# RTI-Dome-Shutter-ESP32.net
KiCad netlist of a schematic drawn in EAGLE
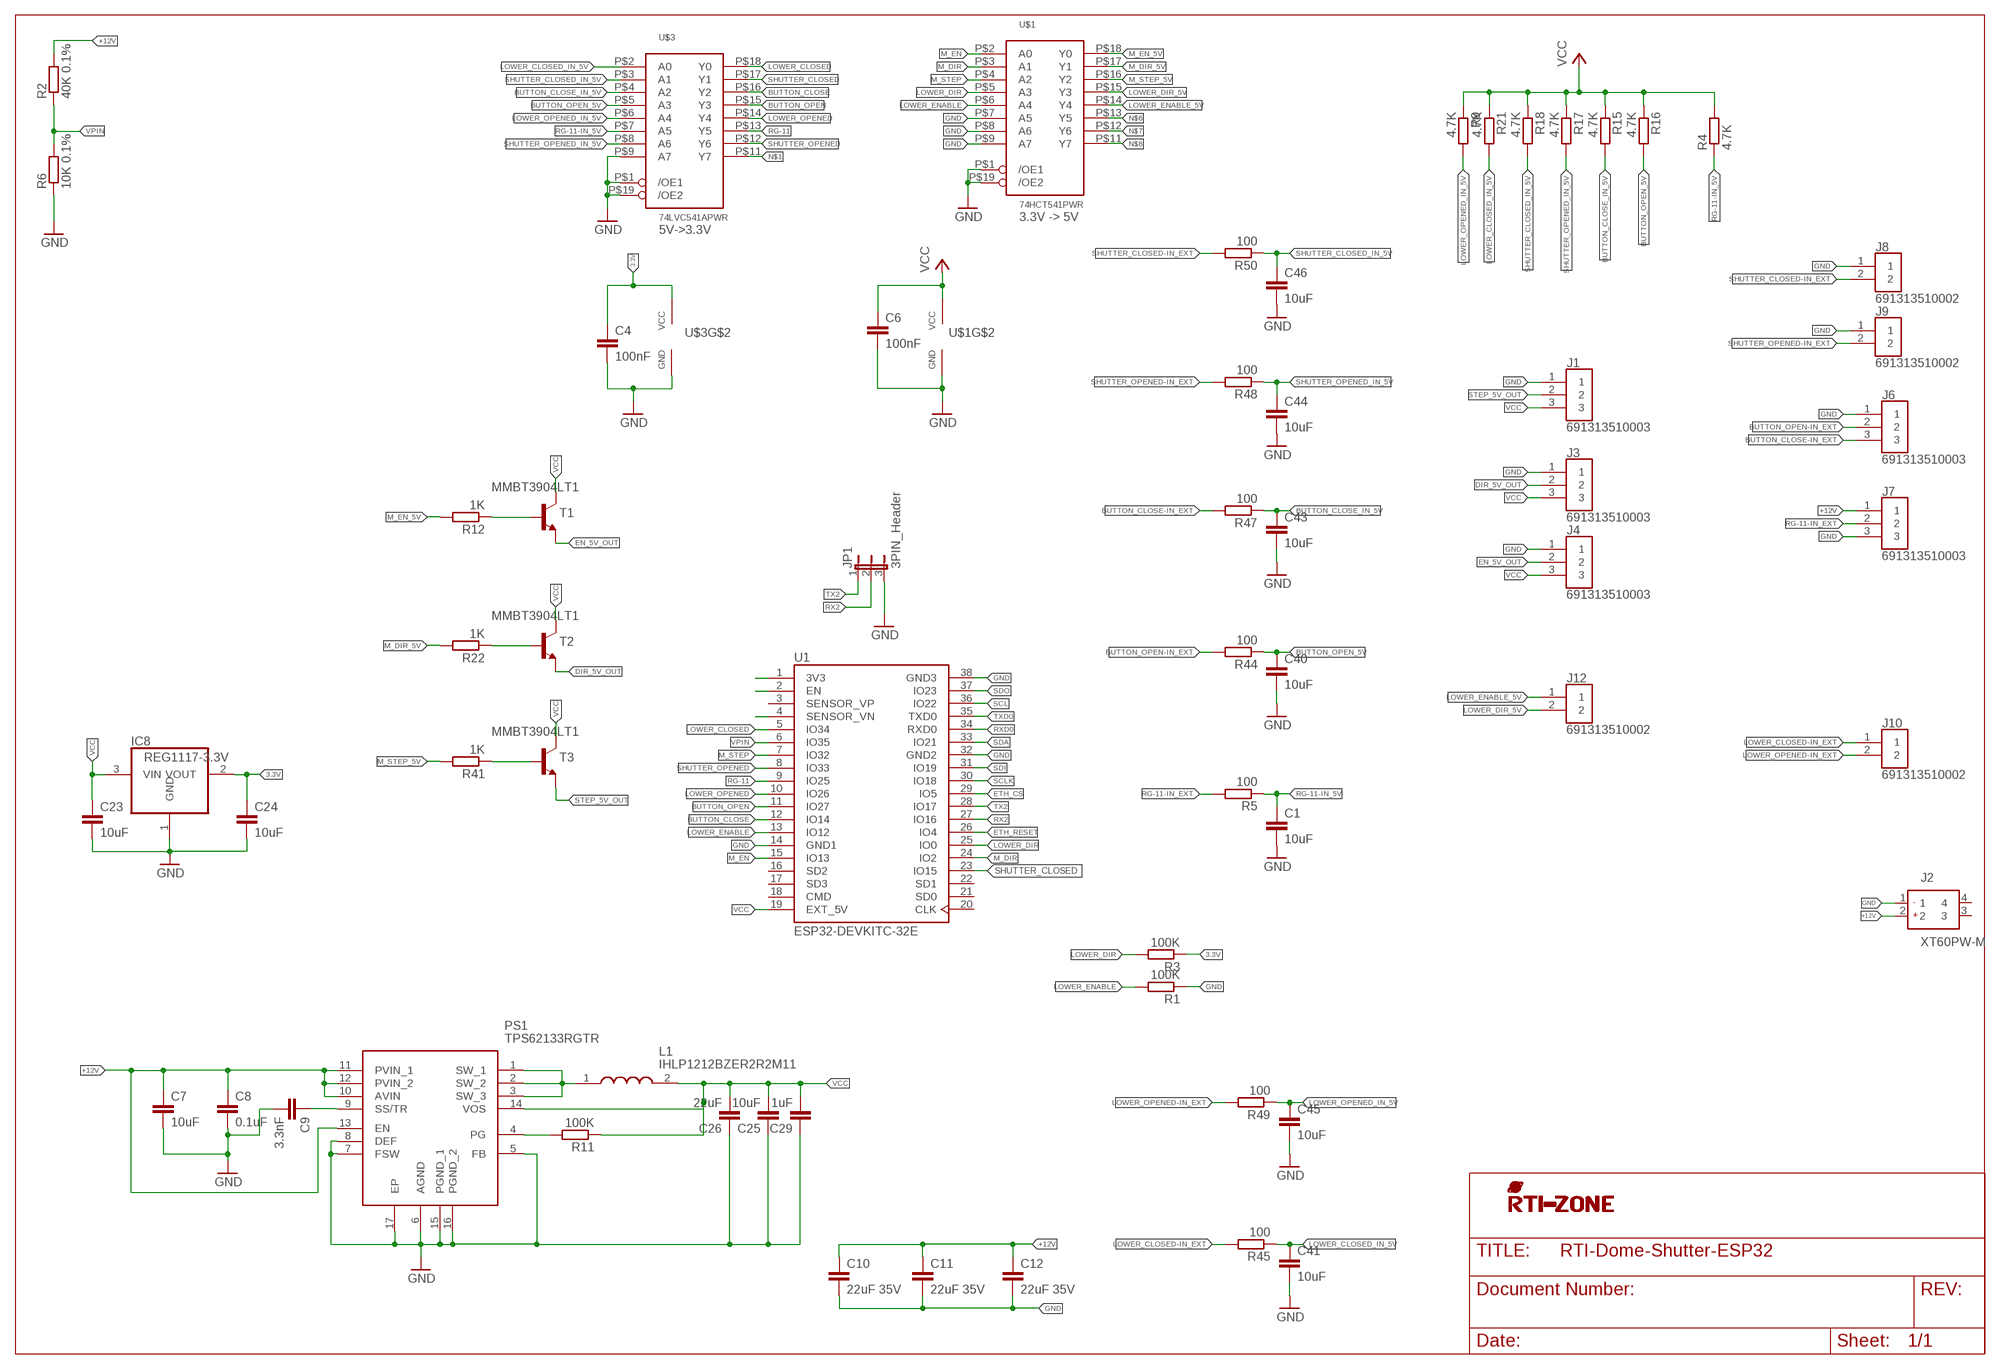
[diagram p0: schematic, sheet 1]

(export (version "E")
  (design (tool "Eeschema 10.0.6"))
  (components
    (comp (ref "C1")
      (value "10uF")
      (footprint "eagle-import:C0603")
      (fields (field (name "MPN") "CC0805KKX5R8BB106"))
      (libsource (lib "eagle-import") (part "C-EU'0603'"))
    )
    (comp (ref "C4")
      (value "100nF")
      (footprint "eagle-import:C0603")
      (fields (field (name "MPN") "0805YD104KAT2A"))
      (libsource (lib "eagle-import") (part "C-EU'0603'"))
    )
    (comp (ref "C6")
      (value "100nF")
      (footprint "eagle-import:C0603")
      (fields (field (name "MPN") "0805YD104KAT2A"))
      (libsource (lib "eagle-import") (part "C-EU'0603'"))
    )
    (comp (ref "C7")
      (value "10uF")
      (footprint "eagle-import:C1206")
      (libsource (lib "eagle-import") (part "C-EUC1206"))
    )
    (comp (ref "C8")
      (value "0.1uF")
      (footprint "eagle-import:C1206")
      (libsource (lib "eagle-import") (part "C-EUC1206"))
    )
    (comp (ref "C9")
      (value "3.3nF")
      (footprint "eagle-import:C0805")
      (libsource (lib "eagle-import") (part "C-EUC0805"))
    )
    (comp (ref "C10")
      (value "22uF 35V")
      (footprint "eagle-import:C1206")
      (libsource (lib "eagle-import") (part "C-EUC1206"))
    )
    (comp (ref "C11")
      (value "22uF 35V")
      (footprint "eagle-import:C1206")
      (libsource (lib "eagle-import") (part "C-EUC1206"))
    )
    (comp (ref "C12")
      (value "22uF 35V")
      (footprint "eagle-import:C1206")
      (libsource (lib "eagle-import") (part "C-EUC1206"))
    )
    (comp (ref "C23")
      (value "10uF")
      (footprint "eagle-import:C0603")
      (fields (field (name "MPN") "CC0805KKX5R8BB106"))
      (libsource (lib "eagle-import") (part "C-EU'0603'"))
    )
    (comp (ref "C24")
      (value "10uF")
      (footprint "eagle-import:C0603")
      (fields (field (name "MPN") "CC0805KKX5R8BB106"))
      (libsource (lib "eagle-import") (part "C-EU'0603'"))
    )
    (comp (ref "C25")
      (value "10uF")
      (footprint "eagle-import:C0805")
      (libsource (lib "eagle-import") (part "C-EUC0805"))
    )
    (comp (ref "C26")
      (value "22uF")
      (footprint "eagle-import:C0805")
      (libsource (lib "eagle-import") (part "C-EUC0805"))
    )
    (comp (ref "C29")
      (value "1uF")
      (footprint "eagle-import:C0805")
      (libsource (lib "eagle-import") (part "C-EUC0805"))
    )
    (comp (ref "C40")
      (value "10uF")
      (footprint "eagle-import:C0603")
      (fields (field (name "MPN") "CC0805KKX5R8BB106"))
      (libsource (lib "eagle-import") (part "C-EU'0603'"))
    )
    (comp (ref "C41")
      (value "10uF")
      (footprint "eagle-import:C0603")
      (fields (field (name "MPN") "CC0805KKX5R8BB106"))
      (libsource (lib "eagle-import") (part "C-EU'0603'"))
    )
    (comp (ref "C43")
      (value "10uF")
      (footprint "eagle-import:C0603")
      (fields (field (name "MPN") "CC0805KKX5R8BB106"))
      (libsource (lib "eagle-import") (part "C-EU'0603'"))
    )
    (comp (ref "C44")
      (value "10uF")
      (footprint "eagle-import:C0603")
      (fields (field (name "MPN") "CC0805KKX5R8BB106"))
      (libsource (lib "eagle-import") (part "C-EU'0603'"))
    )
    (comp (ref "C45")
      (value "10uF")
      (footprint "eagle-import:C0603")
      (fields (field (name "MPN") "CC0805KKX5R8BB106"))
      (libsource (lib "eagle-import") (part "C-EU'0603'"))
    )
    (comp (ref "C46")
      (value "10uF")
      (footprint "eagle-import:C0603")
      (fields (field (name "MPN") "CC0805KKX5R8BB106"))
      (libsource (lib "eagle-import") (part "C-EU'0603'"))
    )
    (comp (ref "IC8")
      (value "REG1117-3.3V")
      (footprint "eagle-import:SOT223")
      (fields (field (name "MPN") "REG1117") (field (name "MPN_1") "REG1117-3.3/2K5"))
      (libsource (lib "eagle-import") (part "REG1117"))
    )
    (comp (ref "J1")
      (value "691313510003")
      (footprint "eagle-import:691313510003")
      (fields (field (name "MOUSER_PART_NUMBER") "710-691313510003"))
      (libsource (lib "eagle-import") (part "691313510003"))
    )
    (comp (ref "J2")
      (value "XT60PW-M")
      (footprint "eagle-import:XT60PWM")
      (fields (field (name "LCSC_PART") "C98732"))
      (libsource (lib "eagle-import") (part "XT60PW-M"))
    )
    (comp (ref "J3")
      (value "691313510003")
      (footprint "eagle-import:691313510003")
      (fields (field (name "MOUSER_PART_NUMBER") "710-691313510003"))
      (libsource (lib "eagle-import") (part "691313510003"))
    )
    (comp (ref "J4")
      (value "691313510003")
      (footprint "eagle-import:691313510003")
      (fields (field (name "MOUSER_PART_NUMBER") "710-691313510003"))
      (libsource (lib "eagle-import") (part "691313510003"))
    )
    (comp (ref "J6")
      (value "691313510003")
      (footprint "eagle-import:691313510003")
      (fields (field (name "MOUSER_PART_NUMBER") "710-691313510003"))
      (libsource (lib "eagle-import") (part "691313510003"))
    )
    (comp (ref "J7")
      (value "691313510003")
      (footprint "eagle-import:691313510003")
      (fields (field (name "MOUSER_PART_NUMBER") "710-691313510003"))
      (libsource (lib "eagle-import") (part "691313510003"))
    )
    (comp (ref "J8")
      (value "691313510002")
      (footprint "eagle-import:SHDRRA2W100P0X508_1X2_1216X120")
      (fields (field (name "MOUSER_PART_NUMBER") "710-691313510002"))
      (libsource (lib "eagle-import") (part "691313510002"))
    )
    (comp (ref "J9")
      (value "691313510002")
      (footprint "eagle-import:SHDRRA2W100P0X508_1X2_1216X120")
      (fields (field (name "MOUSER_PART_NUMBER") "710-691313510002"))
      (libsource (lib "eagle-import") (part "691313510002"))
    )
    (comp (ref "J10")
      (value "691313510002")
      (footprint "eagle-import:SHDRRA2W100P0X508_1X2_1216X120")
      (fields (field (name "MOUSER_PART_NUMBER") "710-691313510002"))
      (libsource (lib "eagle-import") (part "691313510002"))
    )
    (comp (ref "J12")
      (value "691313510002")
      (footprint "eagle-import:SHDRRA2W100P0X508_1X2_1216X120")
      (fields (field (name "MOUSER_PART_NUMBER") "710-691313510002"))
      (libsource (lib "eagle-import") (part "691313510002"))
    )
    (comp (ref "JP1")
      (value "3PIN_Header")
      (footprint "eagle-import:JP2")
      (fields (field (name "LCSC_PART") "C19190477"))
      (libsource (lib "eagle-import") (part "JP2E"))
    )
    (comp (ref "L1")
      (value "IHLP1212BZER2R2M11")
      (footprint "eagle-import:INDPM3630X200N")
      (fields (field (name "LCSC_PART") "C553996") (field (name "MOUSER_PART_NUMBER") "70-IHLP1212BZER2R2M1"))
      (libsource (lib "eagle-import") (part "IHLP1212BZER2R2M11"))
    )
    (comp (ref "PS1")
      (value "TPS62133RGTR")
      (footprint "eagle-import:QFN50P300X300X100-17N")
      (fields (field (name "LCSC_PART") "C73973") (field (name "MOUSER_PART_NUMBER") "595-TPS62133RGTR"))
      (libsource (lib "eagle-import") (part "TPS62133RGTR"))
    )
    (comp (ref "R1")
      (value "100K")
      (footprint "eagle-import:R0603")
      (fields (field (name "MPN") "RT0805FRD07100RL"))
      (libsource (lib "eagle-import") (part "R-EU'0603'"))
    )
    (comp (ref "R2")
      (value "40K 0.1%")
      (footprint "eagle-import:R0603")
      (fields (field (name "MPN") "AT0805BRD07100KL"))
      (libsource (lib "eagle-import") (part "R-EU'0603'"))
    )
    (comp (ref "R3")
      (value "100K")
      (footprint "eagle-import:R0603")
      (fields (field (name "MPN") "RT0805FRD07100RL"))
      (libsource (lib "eagle-import") (part "R-EU'0603'"))
    )
    (comp (ref "R4")
      (value "4.7K")
      (footprint "eagle-import:R0603")
      (fields (field (name "MPN") "RT0805FRE074K7L"))
      (libsource (lib "eagle-import") (part "R-EU'0603'"))
    )
    (comp (ref "R5")
      (value "100")
      (footprint "eagle-import:R0603")
      (fields (field (name "MPN") "RT0805FRD07100RL"))
      (libsource (lib "eagle-import") (part "R-EU'0603'"))
    )
    (comp (ref "R6")
      (value "10K 0.1%")
      (footprint "eagle-import:R0603")
      (fields (field (name "MPN") "AT0805BRD07100KL"))
      (libsource (lib "eagle-import") (part "R-EU'0603'"))
    )
    (comp (ref "R9")
      (value "4.7K")
      (footprint "eagle-import:R0603")
      (fields (field (name "MPN") "RT0805FRE074K7L"))
      (libsource (lib "eagle-import") (part "R-EU'0603'"))
    )
    (comp (ref "R11")
      (value "100K")
      (footprint "eagle-import:R0603")
      (libsource (lib "eagle-import") (part "R-EU_R0603"))
    )
    (comp (ref "R12")
      (value "1K")
      (footprint "eagle-import:R0603")
      (fields (field (name "MPN") "RT0805FRE074K7L"))
      (libsource (lib "eagle-import") (part "R-EU'0603'"))
    )
    (comp (ref "R15")
      (value "4.7K")
      (footprint "eagle-import:R0603")
      (fields (field (name "MPN") "RT0805FRE074K7L"))
      (libsource (lib "eagle-import") (part "R-EU'0603'"))
    )
    (comp (ref "R16")
      (value "4.7K")
      (footprint "eagle-import:R0603")
      (fields (field (name "MPN") "RT0805FRE074K7L"))
      (libsource (lib "eagle-import") (part "R-EU'0603'"))
    )
    (comp (ref "R17")
      (value "4.7K")
      (footprint "eagle-import:R0603")
      (fields (field (name "MPN") "RT0805FRE074K7L"))
      (libsource (lib "eagle-import") (part "R-EU'0603'"))
    )
    (comp (ref "R18")
      (value "4.7K")
      (footprint "eagle-import:R0603")
      (fields (field (name "MPN") "RT0805FRE074K7L"))
      (libsource (lib "eagle-import") (part "R-EU'0603'"))
    )
    (comp (ref "R21")
      (value "4.7K")
      (footprint "eagle-import:R0603")
      (fields (field (name "MPN") "RT0805FRE074K7L"))
      (libsource (lib "eagle-import") (part "R-EU'0603'"))
    )
    (comp (ref "R22")
      (value "1K")
      (footprint "eagle-import:R0603")
      (fields (field (name "MPN") "RT0805FRE074K7L"))
      (libsource (lib "eagle-import") (part "R-EU'0603'"))
    )
    (comp (ref "R41")
      (value "1K")
      (footprint "eagle-import:R0603")
      (fields (field (name "MPN") "RT0805FRE074K7L"))
      (libsource (lib "eagle-import") (part "R-EU'0603'"))
    )
    (comp (ref "R44")
      (value "100")
      (footprint "eagle-import:R0603")
      (fields (field (name "MPN") "RT0805FRD07100RL"))
      (libsource (lib "eagle-import") (part "R-EU'0603'"))
    )
    (comp (ref "R45")
      (value "100")
      (footprint "eagle-import:R0603")
      (fields (field (name "MPN") "RT0805FRD07100RL"))
      (libsource (lib "eagle-import") (part "R-EU'0603'"))
    )
    (comp (ref "R47")
      (value "100")
      (footprint "eagle-import:R0603")
      (fields (field (name "MPN") "RT0805FRD07100RL"))
      (libsource (lib "eagle-import") (part "R-EU'0603'"))
    )
    (comp (ref "R48")
      (value "100")
      (footprint "eagle-import:R0603")
      (fields (field (name "MPN") "RT0805FRD07100RL"))
      (libsource (lib "eagle-import") (part "R-EU'0603'"))
    )
    (comp (ref "R49")
      (value "100")
      (footprint "eagle-import:R0603")
      (fields (field (name "MPN") "RT0805FRD07100RL"))
      (libsource (lib "eagle-import") (part "R-EU'0603'"))
    )
    (comp (ref "R50")
      (value "100")
      (footprint "eagle-import:R0603")
      (fields (field (name "MPN") "RT0805FRD07100RL"))
      (libsource (lib "eagle-import") (part "R-EU'0603'"))
    )
    (comp (ref "T1")
      (value "MMBT3904LT1")
      (footprint "eagle-import:SOT23-BEC")
      (libsource (lib "eagle-import") (part "-NPN-SOT23-BECMMBT3904LT1"))
    )
    (comp (ref "T2")
      (value "MMBT3904LT1")
      (footprint "eagle-import:SOT23-BEC")
      (libsource (lib "eagle-import") (part "-NPN-SOT23-BECMMBT3904LT1"))
    )
    (comp (ref "T3")
      (value "MMBT3904LT1")
      (footprint "eagle-import:SOT23-BEC")
      (libsource (lib "eagle-import") (part "-NPN-SOT23-BECMMBT3904LT1"))
    )
    (comp (ref "U$1")
      (value "74HCT541PWR")
      (footprint "eagle-import:TSSOP20")
      (libsource (lib "eagle-import") (part "74541B"))
    )
    (comp (ref "U$3")
      (value "74LVC541APWR")
      (footprint "eagle-import:TSSOP20")
      (libsource (lib "eagle-import") (part "74541B"))
    )
    (comp (ref "U$4")
      (value "RTI-LOGO_BIG")
      (footprint "eagle-import:LOGO_BIG")
      (libsource (lib "eagle-import") (part "RTI-LOGO_BIG"))
    )
    (comp (ref "U1")
      (value "ESP32-DEVKITC-32E")
      (footprint "eagle-import:MODULE_ESP32-DEVKITC-32D")
      (fields (field (name "MF") "Espressif Systems") (field (name "MP") "ESP32-DEVKITC-32D"))
      (libsource (lib "eagle-import") (part "ESP32-DEVKITC-32D"))
    )
  )
  (nets
    (net (code "1") (name "+12V") (class "Default")
      (node (ref "C10") (pin "1") (pinfunction "1_1") (pintype "passive"))
      (node (ref "C11") (pin "1") (pinfunction "1_1") (pintype "passive"))
      (node (ref "C12") (pin "1") (pinfunction "1_1") (pintype "passive"))
      (node (ref "C7") (pin "1") (pinfunction "1_1") (pintype "passive"))
      (node (ref "C8") (pin "1") (pinfunction "1_1") (pintype "passive"))
      (node (ref "J2") (pin "2") (pinfunction "2_2") (pintype "bidirectional"))
      (node (ref "J7") (pin "1") (pinfunction "1_1") (pintype "bidirectional"))
      (node (ref "PS1") (pin "10") (pinfunction "AVIN_10") (pintype "bidirectional"))
      (node (ref "PS1") (pin "11") (pinfunction "PVIN_1_11") (pintype "bidirectional"))
      (node (ref "PS1") (pin "12") (pinfunction "PVIN_2_12") (pintype "bidirectional"))
      (node (ref "PS1") (pin "13") (pinfunction "EN_13") (pintype "bidirectional"))
      (node (ref "R2") (pin "2") (pinfunction "2_2") (pintype "passive"))
    )
    (net (code "2") (name "3.3V") (class "Default")
      (node (ref "C24") (pin "1") (pinfunction "1_1") (pintype "passive"))
      (node (ref "C4") (pin "1") (pinfunction "1_1") (pintype "passive"))
      (node (ref "IC8") (pin "2") (pinfunction "VOUT_2") (pintype "output"))
      (node (ref "R3") (pin "1") (pinfunction "1_1") (pintype "passive"))
      (node (ref "U$3") (pin "P$20") (pinfunction "VCC_P$20") (pintype "power_in"))
    )
    (net (code "3") (name "BUTTON_CLOSE") (class "Default")
      (node (ref "U$3") (pin "P$16") (pinfunction "Y2_P$16") (pintype "output"))
      (node (ref "U1") (pin "12") (pinfunction "IO14_12") (pintype "bidirectional"))
    )
    (net (code "4") (name "BUTTON_CLOSE-IN_EXT") (class "Default")
      (node (ref "J6") (pin "3") (pinfunction "3_3") (pintype "bidirectional"))
      (node (ref "R47") (pin "2") (pinfunction "2_2") (pintype "passive"))
    )
    (net (code "5") (name "BUTTON_CLOSE_IN_5V") (class "Default")
      (node (ref "C43") (pin "1") (pinfunction "1_1") (pintype "passive"))
      (node (ref "R15") (pin "2") (pinfunction "2_2") (pintype "passive"))
      (node (ref "R47") (pin "1") (pinfunction "1_1") (pintype "passive"))
      (node (ref "U$3") (pin "P$4") (pinfunction "A2_P$4") (pintype "input"))
    )
    (net (code "6") (name "BUTTON_OPEN") (class "Default")
      (node (ref "U$3") (pin "P$15") (pinfunction "Y3_P$15") (pintype "output"))
      (node (ref "U1") (pin "11") (pinfunction "IO27_11") (pintype "bidirectional"))
    )
    (net (code "7") (name "BUTTON_OPEN-IN_EXT") (class "Default")
      (node (ref "J6") (pin "2") (pinfunction "2_2") (pintype "bidirectional"))
      (node (ref "R44") (pin "2") (pinfunction "2_2") (pintype "passive"))
    )
    (net (code "8") (name "BUTTON_OPEN_5V") (class "Default")
      (node (ref "C40") (pin "1") (pinfunction "1_1") (pintype "passive"))
      (node (ref "R16") (pin "2") (pinfunction "2_2") (pintype "passive"))
      (node (ref "R44") (pin "1") (pinfunction "1_1") (pintype "passive"))
      (node (ref "U$3") (pin "P$5") (pinfunction "A3_P$5") (pintype "input"))
    )
    (net (code "9") (name "DIR_5V_OUT") (class "Default")
      (node (ref "J3") (pin "2") (pinfunction "2_2") (pintype "bidirectional"))
      (node (ref "T2") (pin "E") (pinfunction "E_E") (pintype "passive"))
    )
    (net (code "10") (name "EN_5V_OUT") (class "Default")
      (node (ref "J4") (pin "2") (pinfunction "2_2") (pintype "bidirectional"))
      (node (ref "T1") (pin "E") (pinfunction "E_E") (pintype "passive"))
    )
    (net (code "11") (name "ETH_CS") (class "Default")
      (node (ref "U1") (pin "29") (pinfunction "IO5_29") (pintype "bidirectional"))
    )
    (net (code "12") (name "ETH_RESET") (class "Default")
      (node (ref "U1") (pin "26") (pinfunction "IO4_26") (pintype "bidirectional"))
    )
    (net (code "13") (name "GND") (class "Default")
      (node (ref "C1") (pin "2") (pinfunction "2_2") (pintype "passive"))
      (node (ref "C10") (pin "2") (pinfunction "2_2") (pintype "passive"))
      (node (ref "C11") (pin "2") (pinfunction "2_2") (pintype "passive"))
      (node (ref "C12") (pin "2") (pinfunction "2_2") (pintype "passive"))
      (node (ref "C23") (pin "2") (pinfunction "2_2") (pintype "passive"))
      (node (ref "C24") (pin "2") (pinfunction "2_2") (pintype "passive"))
      (node (ref "C25") (pin "1") (pinfunction "1_1") (pintype "passive"))
      (node (ref "C26") (pin "1") (pinfunction "1_1") (pintype "passive"))
      (node (ref "C29") (pin "1") (pinfunction "1_1") (pintype "passive"))
      (node (ref "C4") (pin "2") (pinfunction "2_2") (pintype "passive"))
      (node (ref "C40") (pin "2") (pinfunction "2_2") (pintype "passive"))
      (node (ref "C41") (pin "2") (pinfunction "2_2") (pintype "passive"))
      (node (ref "C43") (pin "2") (pinfunction "2_2") (pintype "passive"))
      (node (ref "C44") (pin "2") (pinfunction "2_2") (pintype "passive"))
      (node (ref "C45") (pin "2") (pinfunction "2_2") (pintype "passive"))
      (node (ref "C46") (pin "2") (pinfunction "2_2") (pintype "passive"))
      (node (ref "C6") (pin "2") (pinfunction "2_2") (pintype "passive"))
      (node (ref "C7") (pin "2") (pinfunction "2_2") (pintype "passive"))
      (node (ref "C8") (pin "2") (pinfunction "2_2") (pintype "passive"))
      (node (ref "C9") (pin "2") (pinfunction "2_2") (pintype "passive"))
      (node (ref "IC8") (pin "1") (pinfunction "GND_1") (pintype "power_in"))
      (node (ref "J1") (pin "1") (pinfunction "1_1") (pintype "bidirectional"))
      (node (ref "J2") (pin "1") (pinfunction "1_1") (pintype "bidirectional"))
      (node (ref "J3") (pin "1") (pinfunction "1_1") (pintype "bidirectional"))
      (node (ref "J4") (pin "1") (pinfunction "1_1") (pintype "bidirectional"))
      (node (ref "J6") (pin "1") (pinfunction "1_1") (pintype "bidirectional"))
      (node (ref "J7") (pin "3") (pinfunction "3_3") (pintype "bidirectional"))
      (node (ref "J8") (pin "1") (pinfunction "1_1") (pintype "bidirectional"))
      (node (ref "J9") (pin "1") (pinfunction "1_1") (pintype "bidirectional"))
      (node (ref "JP1") (pin "3") (pinfunction "3_3") (pintype "passive"))
      (node (ref "PS1") (pin "15") (pinfunction "PGND_1_15") (pintype "bidirectional"))
      (node (ref "PS1") (pin "16") (pinfunction "PGND_2_16") (pintype "bidirectional"))
      (node (ref "PS1") (pin "17") (pinfunction "EP_17") (pintype "bidirectional"))
      (node (ref "PS1") (pin "5") (pinfunction "FB_5") (pintype "bidirectional"))
      (node (ref "PS1") (pin "6") (pinfunction "AGND_6") (pintype "bidirectional"))
      (node (ref "PS1") (pin "7") (pinfunction "FSW_7") (pintype "bidirectional"))
      (node (ref "PS1") (pin "8") (pinfunction "DEF_8") (pintype "bidirectional"))
      (node (ref "R1") (pin "1") (pinfunction "1_1") (pintype "passive"))
      (node (ref "R6") (pin "1") (pinfunction "1_1") (pintype "passive"))
      (node (ref "U$1") (pin "P$1") (pinfunction "/OE1_P$1") (pintype "input"))
      (node (ref "U$1") (pin "P$10") (pinfunction "GND_P$10") (pintype "power_in"))
      (node (ref "U$1") (pin "P$19") (pinfunction "/OE2_P$19") (pintype "input"))
      (node (ref "U$1") (pin "P$7") (pinfunction "A5_P$7") (pintype "input"))
      (node (ref "U$1") (pin "P$8") (pinfunction "A6_P$8") (pintype "input"))
      (node (ref "U$1") (pin "P$9") (pinfunction "A7_P$9") (pintype "input"))
      (node (ref "U$3") (pin "P$1") (pinfunction "/OE1_P$1") (pintype "input"))
      (node (ref "U$3") (pin "P$10") (pinfunction "GND_P$10") (pintype "power_in"))
      (node (ref "U$3") (pin "P$19") (pinfunction "/OE2_P$19") (pintype "input"))
      (node (ref "U$3") (pin "P$9") (pinfunction "A7_P$9") (pintype "input"))
      (node (ref "U1") (pin "14") (pinfunction "GND1_14") (pintype "power_in"))
      (node (ref "U1") (pin "32") (pinfunction "GND2_32") (pintype "power_in"))
      (node (ref "U1") (pin "38") (pinfunction "GND3_38") (pintype "power_in"))
    )
    (net (code "14") (name "LOWER_CLOSED") (class "Default")
      (node (ref "U$3") (pin "P$18") (pinfunction "Y0_P$18") (pintype "output"))
      (node (ref "U1") (pin "5") (pinfunction "IO34_5") (pintype "bidirectional"))
    )
    (net (code "15") (name "LOWER_CLOSED-IN_EXT") (class "Default")
      (node (ref "J10") (pin "1") (pinfunction "1_1") (pintype "bidirectional"))
      (node (ref "R45") (pin "2") (pinfunction "2_2") (pintype "passive"))
    )
    (net (code "16") (name "LOWER_CLOSED_IN_5V") (class "Default")
      (node (ref "C41") (pin "1") (pinfunction "1_1") (pintype "passive"))
      (node (ref "R21") (pin "2") (pinfunction "2_2") (pintype "passive"))
      (node (ref "R45") (pin "1") (pinfunction "1_1") (pintype "passive"))
      (node (ref "U$3") (pin "P$2") (pinfunction "A0_P$2") (pintype "input"))
    )
    (net (code "17") (name "LOWER_DIR") (class "Default")
      (node (ref "R3") (pin "2") (pinfunction "2_2") (pintype "passive"))
      (node (ref "U$1") (pin "P$5") (pinfunction "A3_P$5") (pintype "input"))
      (node (ref "U1") (pin "25") (pinfunction "IO0_25") (pintype "bidirectional"))
    )
    (net (code "18") (name "LOWER_DIR_5V") (class "Default")
      (node (ref "J12") (pin "2") (pinfunction "2_2") (pintype "bidirectional"))
      (node (ref "U$1") (pin "P$15") (pinfunction "Y3_P$15") (pintype "output"))
    )
    (net (code "19") (name "LOWER_ENABLE") (class "Default")
      (node (ref "R1") (pin "2") (pinfunction "2_2") (pintype "passive"))
      (node (ref "U$1") (pin "P$6") (pinfunction "A4_P$6") (pintype "input"))
      (node (ref "U1") (pin "13") (pinfunction "IO12_13") (pintype "bidirectional"))
    )
    (net (code "20") (name "LOWER_ENABLE_5V") (class "Default")
      (node (ref "J12") (pin "1") (pinfunction "1_1") (pintype "bidirectional"))
      (node (ref "U$1") (pin "P$14") (pinfunction "Y4_P$14") (pintype "output"))
    )
    (net (code "21") (name "LOWER_OPENED") (class "Default")
      (node (ref "U$3") (pin "P$14") (pinfunction "Y4_P$14") (pintype "output"))
      (node (ref "U1") (pin "10") (pinfunction "IO26_10") (pintype "bidirectional"))
    )
    (net (code "22") (name "LOWER_OPENED-IN_EXT") (class "Default")
      (node (ref "J10") (pin "2") (pinfunction "2_2") (pintype "bidirectional"))
      (node (ref "R49") (pin "2") (pinfunction "2_2") (pintype "passive"))
    )
    (net (code "23") (name "LOWER_OPENED_IN_5V") (class "Default")
      (node (ref "C45") (pin "1") (pinfunction "1_1") (pintype "passive"))
      (node (ref "R49") (pin "1") (pinfunction "1_1") (pintype "passive"))
      (node (ref "R9") (pin "2") (pinfunction "2_2") (pintype "passive"))
      (node (ref "U$3") (pin "P$6") (pinfunction "A4_P$6") (pintype "input"))
    )
    (net (code "24") (name "M_DIR") (class "Default")
      (node (ref "U$1") (pin "P$3") (pinfunction "A1_P$3") (pintype "input"))
      (node (ref "U1") (pin "24") (pinfunction "IO2_24") (pintype "bidirectional"))
    )
    (net (code "25") (name "M_DIR_5V") (class "Default")
      (node (ref "R22") (pin "2") (pinfunction "2_2") (pintype "passive"))
      (node (ref "U$1") (pin "P$17") (pinfunction "Y1_P$17") (pintype "output"))
    )
    (net (code "26") (name "M_EN") (class "Default")
      (node (ref "U$1") (pin "P$2") (pinfunction "A0_P$2") (pintype "input"))
      (node (ref "U1") (pin "15") (pinfunction "IO13_15") (pintype "bidirectional"))
    )
    (net (code "27") (name "M_EN_5V") (class "Default")
      (node (ref "R12") (pin "2") (pinfunction "2_2") (pintype "passive"))
      (node (ref "U$1") (pin "P$18") (pinfunction "Y0_P$18") (pintype "output"))
    )
    (net (code "28") (name "M_STEP") (class "Default")
      (node (ref "U$1") (pin "P$4") (pinfunction "A2_P$4") (pintype "input"))
      (node (ref "U1") (pin "7") (pinfunction "IO32_7") (pintype "bidirectional"))
    )
    (net (code "29") (name "M_STEP_5V") (class "Default")
      (node (ref "R41") (pin "2") (pinfunction "2_2") (pintype "passive"))
      (node (ref "U$1") (pin "P$16") (pinfunction "Y2_P$16") (pintype "output"))
    )
    (net (code "30") (name "N$1") (class "Default")
      (node (ref "U$3") (pin "P$11") (pinfunction "Y7_P$11") (pintype "output"))
    )
    (net (code "31") (name "N$6") (class "Default")
      (node (ref "U$1") (pin "P$13") (pinfunction "Y5_P$13") (pintype "output"))
    )
    (net (code "32") (name "N$7") (class "Default")
      (node (ref "U$1") (pin "P$12") (pinfunction "Y6_P$12") (pintype "output"))
    )
    (net (code "33") (name "N$8") (class "Default")
      (node (ref "U$1") (pin "P$11") (pinfunction "Y7_P$11") (pintype "output"))
    )
    (net (code "34") (name "Net-(PS1-PG)") (class "Default")
      (node (ref "PS1") (pin "4") (pinfunction "PG_4") (pintype "bidirectional"))
      (node (ref "R11") (pin "2") (pinfunction "2_2") (pintype "passive"))
    )
    (net (code "35") (name "Net-(PS1-SS{slash}TR)") (class "Default")
      (node (ref "C9") (pin "1") (pinfunction "1_1") (pintype "passive"))
      (node (ref "PS1") (pin "9") (pinfunction "SS/TR_9") (pintype "bidirectional"))
    )
    (net (code "36") (name "Net-(PS1-SW_1)") (class "Default")
      (node (ref "L1") (pin "1") (pinfunction "1_1") (pintype "bidirectional"))
      (node (ref "PS1") (pin "1") (pinfunction "SW_1_1") (pintype "bidirectional"))
      (node (ref "PS1") (pin "2") (pinfunction "SW_2_2") (pintype "bidirectional"))
      (node (ref "PS1") (pin "3") (pinfunction "SW_3_3") (pintype "bidirectional"))
    )
    (net (code "37") (name "Net-(R12-Pad1)") (class "Default")
      (node (ref "R12") (pin "1") (pinfunction "1_1") (pintype "passive"))
      (node (ref "T1") (pin "B") (pinfunction "B_B") (pintype "passive"))
    )
    (net (code "38") (name "Net-(R22-Pad1)") (class "Default")
      (node (ref "R22") (pin "1") (pinfunction "1_1") (pintype "passive"))
      (node (ref "T2") (pin "B") (pinfunction "B_B") (pintype "passive"))
    )
    (net (code "39") (name "Net-(R41-Pad1)") (class "Default")
      (node (ref "R41") (pin "1") (pinfunction "1_1") (pintype "passive"))
      (node (ref "T3") (pin "B") (pinfunction "B_B") (pintype "passive"))
    )
    (net (code "40") (name "RG-11") (class "Default")
      (node (ref "U$3") (pin "P$13") (pinfunction "Y5_P$13") (pintype "output"))
      (node (ref "U1") (pin "9") (pinfunction "IO25_9") (pintype "bidirectional"))
    )
    (net (code "41") (name "RG-11-IN_5V") (class "Default")
      (node (ref "C1") (pin "1") (pinfunction "1_1") (pintype "passive"))
      (node (ref "R4") (pin "1") (pinfunction "1_1") (pintype "passive"))
      (node (ref "R5") (pin "1") (pinfunction "1_1") (pintype "passive"))
      (node (ref "U$3") (pin "P$7") (pinfunction "A5_P$7") (pintype "input"))
    )
    (net (code "42") (name "RG-11-IN_EXT") (class "Default")
      (node (ref "J7") (pin "2") (pinfunction "2_2") (pintype "bidirectional"))
      (node (ref "R5") (pin "2") (pinfunction "2_2") (pintype "passive"))
    )
    (net (code "43") (name "RX2") (class "Default")
      (node (ref "JP1") (pin "2") (pinfunction "2_2") (pintype "passive"))
      (node (ref "U1") (pin "27") (pinfunction "IO16_27") (pintype "bidirectional"))
    )
    (net (code "44") (name "RXD0") (class "Default")
      (node (ref "U1") (pin "34") (pinfunction "RXD0_34") (pintype "input"))
    )
    (net (code "45") (name "SCL") (class "Default")
      (node (ref "U1") (pin "36") (pinfunction "IO22_36") (pintype "bidirectional"))
    )
    (net (code "46") (name "SCLK") (class "Default")
      (node (ref "U1") (pin "30") (pinfunction "IO18_30") (pintype "bidirectional"))
    )
    (net (code "47") (name "SDA") (class "Default")
      (node (ref "U1") (pin "33") (pinfunction "IO21_33") (pintype "bidirectional"))
    )
    (net (code "48") (name "SDI") (class "Default")
      (node (ref "U1") (pin "31") (pinfunction "IO19_31") (pintype "bidirectional"))
    )
    (net (code "49") (name "SDO") (class "Default")
      (node (ref "U1") (pin "37") (pinfunction "IO23_37") (pintype "bidirectional"))
    )
    (net (code "50") (name "SHUTTER_CLOSED") (class "Default")
      (node (ref "U$3") (pin "P$17") (pinfunction "Y1_P$17") (pintype "output"))
      (node (ref "U1") (pin "23") (pinfunction "IO15_23") (pintype "bidirectional"))
    )
    (net (code "51") (name "SHUTTER_CLOSED-IN_EXT") (class "Default")
      (node (ref "J8") (pin "2") (pinfunction "2_2") (pintype "bidirectional"))
      (node (ref "R50") (pin "2") (pinfunction "2_2") (pintype "passive"))
    )
    (net (code "52") (name "SHUTTER_CLOSED_IN_5V") (class "Default")
      (node (ref "C46") (pin "1") (pinfunction "1_1") (pintype "passive"))
      (node (ref "R18") (pin "2") (pinfunction "2_2") (pintype "passive"))
      (node (ref "R50") (pin "1") (pinfunction "1_1") (pintype "passive"))
      (node (ref "U$3") (pin "P$3") (pinfunction "A1_P$3") (pintype "input"))
    )
    (net (code "53") (name "SHUTTER_OPENED") (class "Default")
      (node (ref "U$3") (pin "P$12") (pinfunction "Y6_P$12") (pintype "output"))
      (node (ref "U1") (pin "8") (pinfunction "IO33_8") (pintype "bidirectional"))
    )
    (net (code "54") (name "SHUTTER_OPENED-IN_EXT") (class "Default")
      (node (ref "J9") (pin "2") (pinfunction "2_2") (pintype "bidirectional"))
      (node (ref "R48") (pin "2") (pinfunction "2_2") (pintype "passive"))
    )
    (net (code "55") (name "SHUTTER_OPENED_IN_5V") (class "Default")
      (node (ref "C44") (pin "1") (pinfunction "1_1") (pintype "passive"))
      (node (ref "R17") (pin "2") (pinfunction "2_2") (pintype "passive"))
      (node (ref "R48") (pin "1") (pinfunction "1_1") (pintype "passive"))
      (node (ref "U$3") (pin "P$8") (pinfunction "A6_P$8") (pintype "input"))
    )
    (net (code "56") (name "STEP_5V_OUT") (class "Default")
      (node (ref "J1") (pin "2") (pinfunction "2_2") (pintype "bidirectional"))
      (node (ref "T3") (pin "E") (pinfunction "E_E") (pintype "passive"))
    )
    (net (code "57") (name "TX2") (class "Default")
      (node (ref "JP1") (pin "1") (pinfunction "1_1") (pintype "passive"))
      (node (ref "U1") (pin "28") (pinfunction "IO17_28") (pintype "bidirectional"))
    )
    (net (code "58") (name "TXD0") (class "Default")
      (node (ref "U1") (pin "35") (pinfunction "TXD0_35") (pintype "output"))
    )
    (net (code "59") (name "VCC") (class "Default")
      (node (ref "C23") (pin "1") (pinfunction "1_1") (pintype "passive"))
      (node (ref "C25") (pin "2") (pinfunction "2_2") (pintype "passive"))
      (node (ref "C26") (pin "2") (pinfunction "2_2") (pintype "passive"))
      (node (ref "C29") (pin "2") (pinfunction "2_2") (pintype "passive"))
      (node (ref "C6") (pin "1") (pinfunction "1_1") (pintype "passive"))
      (node (ref "IC8") (pin "3") (pinfunction "VIN_3") (pintype "input"))
      (node (ref "J1") (pin "3") (pinfunction "3_3") (pintype "bidirectional"))
      (node (ref "J3") (pin "3") (pinfunction "3_3") (pintype "bidirectional"))
      (node (ref "J4") (pin "3") (pinfunction "3_3") (pintype "bidirectional"))
      (node (ref "L1") (pin "2") (pinfunction "2_2") (pintype "bidirectional"))
      (node (ref "PS1") (pin "14") (pinfunction "VOS_14") (pintype "bidirectional"))
      (node (ref "R11") (pin "1") (pinfunction "1_1") (pintype "passive"))
      (node (ref "R15") (pin "1") (pinfunction "1_1") (pintype "passive"))
      (node (ref "R16") (pin "1") (pinfunction "1_1") (pintype "passive"))
      (node (ref "R17") (pin "1") (pinfunction "1_1") (pintype "passive"))
      (node (ref "R18") (pin "1") (pinfunction "1_1") (pintype "passive"))
      (node (ref "R21") (pin "1") (pinfunction "1_1") (pintype "passive"))
      (node (ref "R4") (pin "2") (pinfunction "2_2") (pintype "passive"))
      (node (ref "R9") (pin "1") (pinfunction "1_1") (pintype "passive"))
      (node (ref "T1") (pin "C") (pinfunction "C_C") (pintype "passive"))
      (node (ref "T2") (pin "C") (pinfunction "C_C") (pintype "passive"))
      (node (ref "T3") (pin "C") (pinfunction "C_C") (pintype "passive"))
      (node (ref "U$1") (pin "P$20") (pinfunction "VCC_P$20") (pintype "power_in"))
      (node (ref "U1") (pin "19") (pinfunction "EXT_5V_19") (pintype "power_in"))
    )
    (net (code "60") (name "VPIN") (class "Default")
      (node (ref "R2") (pin "1") (pinfunction "1_1") (pintype "passive"))
      (node (ref "R6") (pin "2") (pinfunction "2_2") (pintype "passive"))
      (node (ref "U1") (pin "6") (pinfunction "IO35_6") (pintype "bidirectional"))
    )
    (net (code "61") (name "unconnected-(J2-Pad3)") (class "Default")
      (node (ref "J2") (pin "3") (pinfunction "3_3") (pintype "bidirectional"))
    )
    (net (code "62") (name "unconnected-(J2-Pad4)") (class "Default")
      (node (ref "J2") (pin "4") (pinfunction "4_4") (pintype "bidirectional"))
    )
    (net (code "63") (name "unconnected-(U1-3V3-Pad1)") (class "Default")
      (node (ref "U1") (pin "1") (pinfunction "3V3_1") (pintype "power_in"))
    )
    (net (code "64") (name "unconnected-(U1-CLK-Pad20)") (class "Default")
      (node (ref "U1") (pin "20") (pinfunction "CLK_20") (pintype "input"))
    )
    (net (code "65") (name "unconnected-(U1-CMD-Pad18)") (class "Default")
      (node (ref "U1") (pin "18") (pinfunction "CMD_18") (pintype "bidirectional"))
    )
    (net (code "66") (name "unconnected-(U1-EN-Pad2)") (class "Default")
      (node (ref "U1") (pin "2") (pinfunction "EN_2") (pintype "input"))
    )
    (net (code "67") (name "unconnected-(U1-SD0-Pad21)") (class "Default")
      (node (ref "U1") (pin "21") (pinfunction "SD0_21") (pintype "bidirectional"))
    )
    (net (code "68") (name "unconnected-(U1-SD1-Pad22)") (class "Default")
      (node (ref "U1") (pin "22") (pinfunction "SD1_22") (pintype "bidirectional"))
    )
    (net (code "69") (name "unconnected-(U1-SD2-Pad16)") (class "Default")
      (node (ref "U1") (pin "16") (pinfunction "SD2_16") (pintype "bidirectional"))
    )
    (net (code "70") (name "unconnected-(U1-SD3-Pad17)") (class "Default")
      (node (ref "U1") (pin "17") (pinfunction "SD3_17") (pintype "bidirectional"))
    )
    (net (code "71") (name "unconnected-(U1-SENSOR_VN-Pad4)") (class "Default")
      (node (ref "U1") (pin "4") (pinfunction "SENSOR_VN_4") (pintype "input"))
    )
    (net (code "72") (name "unconnected-(U1-SENSOR_VP-Pad3)") (class "Default")
      (node (ref "U1") (pin "3") (pinfunction "SENSOR_VP_3") (pintype "input"))
    )
  )
)
